# badge.net
KiCad netlist of a schematic drawn in EAGLE
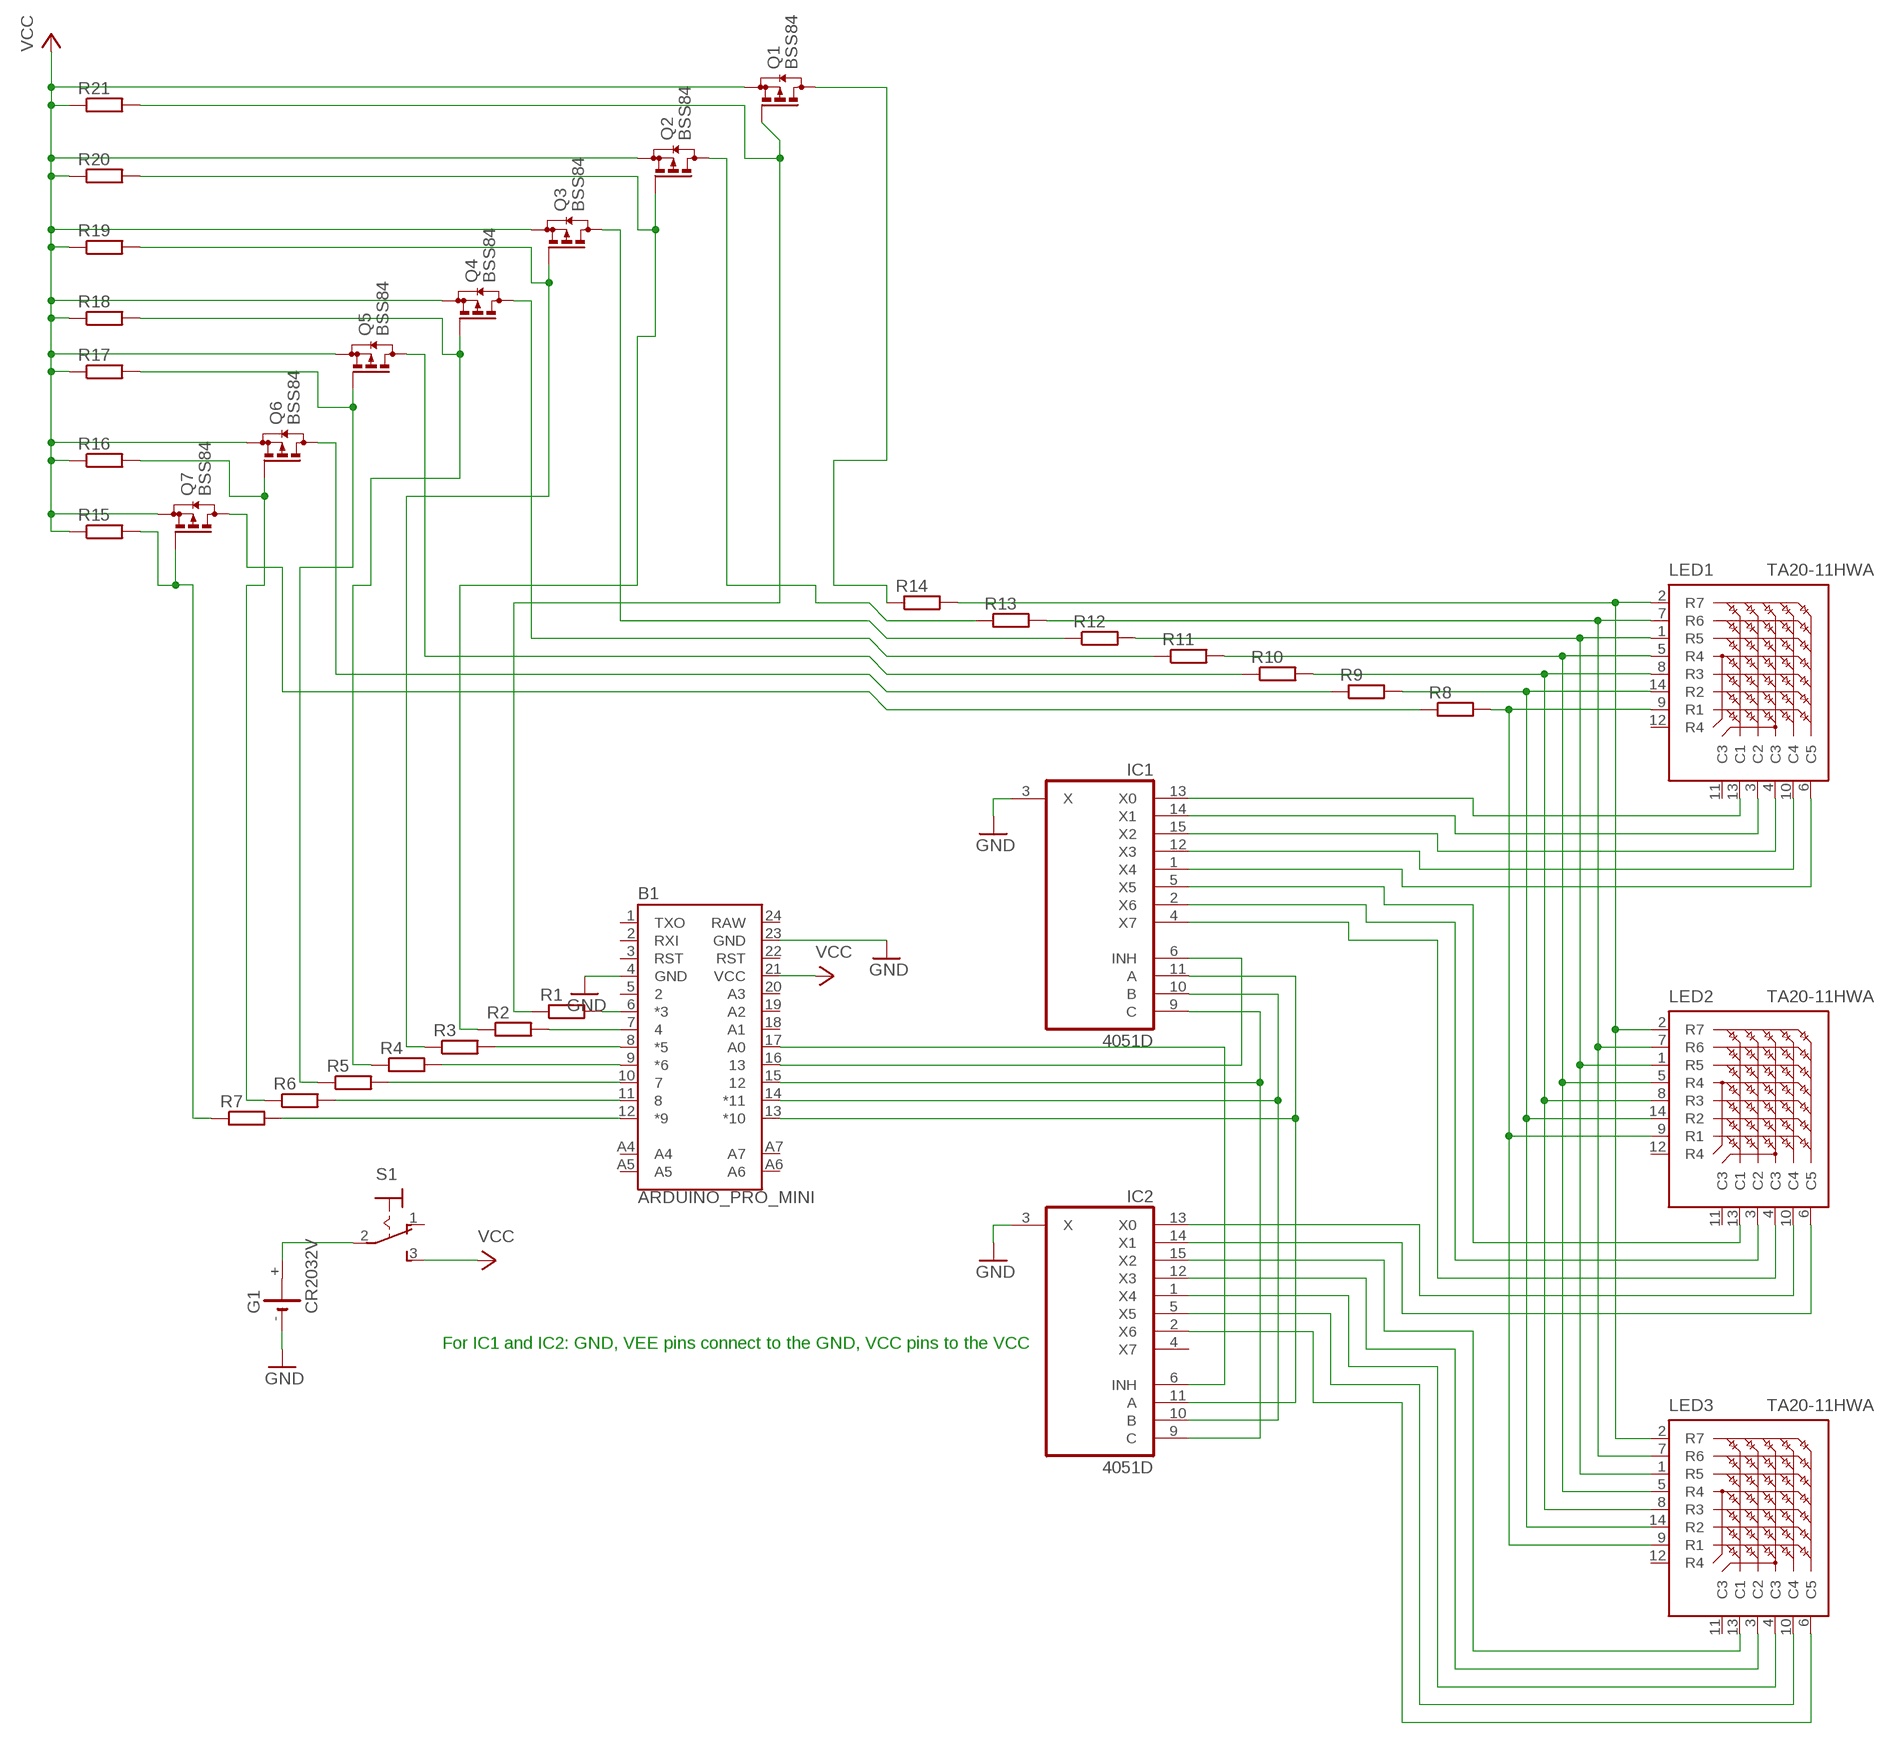
[diagram p0: schematic, sheet 1]

(export (version "E")
  (design (tool "Eeschema 10.0.6"))
  (components
    (comp (ref "B1")
      (value "ARDUINO_PRO_MINI")
      (footprint "eagle-import:ARDUINO_PRO_MINI")
      (libsource (lib "eagle-import") (part "ARDUINO_PRO_MINI"))
    )
    (comp (ref "G1")
      (value "CR2032V")
      (footprint "eagle-import:CR2032V")
      (libsource (lib "eagle-import") (part "CR2032V"))
    )
    (comp (ref "IC1")
      (value "4051D")
      (footprint "eagle-import:SO16")
      (libsource (lib "eagle-import") (part "4051D"))
    )
    (comp (ref "IC2")
      (value "4051D")
      (footprint "eagle-import:SO16")
      (libsource (lib "eagle-import") (part "4051D"))
    )
    (comp (ref "LED1")
      (value "TA20-11HWA")
      (footprint "eagle-import:TA20-11HWA")
      (libsource (lib "eagle-import") (part "TA20-11HWA"))
    )
    (comp (ref "LED2")
      (value "TA20-11HWA")
      (footprint "eagle-import:TA20-11HWA")
      (libsource (lib "eagle-import") (part "TA20-11HWA"))
    )
    (comp (ref "LED3")
      (value "TA20-11HWA")
      (footprint "eagle-import:TA20-11HWA")
      (libsource (lib "eagle-import") (part "TA20-11HWA"))
    )
    (comp (ref "Q1")
      (value "BSS84")
      (footprint "eagle-import:SOT23")
      (libsource (lib "eagle-import") (part "BSS84"))
    )
    (comp (ref "Q2")
      (value "BSS84")
      (footprint "eagle-import:SOT23")
      (libsource (lib "eagle-import") (part "BSS84"))
    )
    (comp (ref "Q3")
      (value "BSS84")
      (footprint "eagle-import:SOT23")
      (libsource (lib "eagle-import") (part "BSS84"))
    )
    (comp (ref "Q4")
      (value "BSS84")
      (footprint "eagle-import:SOT23")
      (libsource (lib "eagle-import") (part "BSS84"))
    )
    (comp (ref "Q5")
      (value "BSS84")
      (footprint "eagle-import:SOT23")
      (libsource (lib "eagle-import") (part "BSS84"))
    )
    (comp (ref "Q6")
      (value "BSS84")
      (footprint "eagle-import:SOT23")
      (libsource (lib "eagle-import") (part "BSS84"))
    )
    (comp (ref "Q7")
      (value "BSS84")
      (footprint "eagle-import:SOT23")
      (libsource (lib "eagle-import") (part "BSS84"))
    )
    (comp (ref "R1")
      (value "R-EU_R0603")
      (footprint "eagle-import:R0603")
      (libsource (lib "eagle-import") (part "R-EU_R0603"))
    )
    (comp (ref "R2")
      (value "R-EU_R0603")
      (footprint "eagle-import:R0603")
      (libsource (lib "eagle-import") (part "R-EU_R0603"))
    )
    (comp (ref "R3")
      (value "R-EU_R0603")
      (footprint "eagle-import:R0603")
      (libsource (lib "eagle-import") (part "R-EU_R0603"))
    )
    (comp (ref "R4")
      (value "R-EU_R0603")
      (footprint "eagle-import:R0603")
      (libsource (lib "eagle-import") (part "R-EU_R0603"))
    )
    (comp (ref "R5")
      (value "R-EU_R0603")
      (footprint "eagle-import:R0603")
      (libsource (lib "eagle-import") (part "R-EU_R0603"))
    )
    (comp (ref "R6")
      (value "R-EU_R0603")
      (footprint "eagle-import:R0603")
      (libsource (lib "eagle-import") (part "R-EU_R0603"))
    )
    (comp (ref "R7")
      (value "R-EU_R0603")
      (footprint "eagle-import:R0603")
      (libsource (lib "eagle-import") (part "R-EU_R0603"))
    )
    (comp (ref "R8")
      (value "R-EU_R0805")
      (footprint "eagle-import:R0805")
      (libsource (lib "eagle-import") (part "resistor_348_R-EU_R0805"))
    )
    (comp (ref "R9")
      (value "R-EU_R0805")
      (footprint "eagle-import:R0805")
      (libsource (lib "eagle-import") (part "resistor_348_R-EU_R0805"))
    )
    (comp (ref "R10")
      (value "R-EU_R0805")
      (footprint "eagle-import:R0805")
      (libsource (lib "eagle-import") (part "resistor_348_R-EU_R0805"))
    )
    (comp (ref "R11")
      (value "R-EU_R0805")
      (footprint "eagle-import:R0805")
      (libsource (lib "eagle-import") (part "resistor_348_R-EU_R0805"))
    )
    (comp (ref "R12")
      (value "R-EU_R0805")
      (footprint "eagle-import:R0805")
      (libsource (lib "eagle-import") (part "resistor_348_R-EU_R0805"))
    )
    (comp (ref "R13")
      (value "R-EU_R0805")
      (footprint "eagle-import:R0805")
      (libsource (lib "eagle-import") (part "resistor_348_R-EU_R0805"))
    )
    (comp (ref "R14")
      (value "R-EU_R0805")
      (footprint "eagle-import:R0805")
      (libsource (lib "eagle-import") (part "resistor_348_R-EU_R0805"))
    )
    (comp (ref "R15")
      (value "R-EU_R0603")
      (footprint "eagle-import:R0603")
      (libsource (lib "eagle-import") (part "resistor_348_R-EU_R0603"))
    )
    (comp (ref "R16")
      (value "R-EU_R0603")
      (footprint "eagle-import:R0603")
      (libsource (lib "eagle-import") (part "resistor_348_R-EU_R0603"))
    )
    (comp (ref "R17")
      (value "R-EU_R0603")
      (footprint "eagle-import:R0603")
      (libsource (lib "eagle-import") (part "resistor_348_R-EU_R0603"))
    )
    (comp (ref "R18")
      (value "R-EU_R0603")
      (footprint "eagle-import:R0603")
      (libsource (lib "eagle-import") (part "resistor_348_R-EU_R0603"))
    )
    (comp (ref "R19")
      (value "R-EU_R0603")
      (footprint "eagle-import:R0603")
      (libsource (lib "eagle-import") (part "resistor_348_R-EU_R0603"))
    )
    (comp (ref "R20")
      (value "R-EU_R0603")
      (footprint "eagle-import:R0603")
      (libsource (lib "eagle-import") (part "resistor_348_R-EU_R0603"))
    )
    (comp (ref "R21")
      (value "R-EU_R0603")
      (footprint "eagle-import:R0603")
      (libsource (lib "eagle-import") (part "resistor_348_R-EU_R0603"))
    )
    (comp (ref "S1")
      (value "320-916")
      (footprint "eagle-import:320-916")
      (libsource (lib "eagle-import") (part "320-916"))
    )
  )
  (nets
    (net (code "1") (name "/RAW") (class "Default")
      (node (ref "B1") (pin "24") (pinfunction "RAW_24") (pintype "power_in"))
    )
    (net (code "2") (name "GND") (class "Default")
      (node (ref "B1") (pin "23") (pinfunction "GND_23") (pintype "power_in"))
      (node (ref "B1") (pin "4") (pinfunction "GND_4") (pintype "power_in"))
      (node (ref "G1") (pin "-") (pinfunction "-_-") (pintype "passive"))
      (node (ref "IC1") (pin "3") (pinfunction "X_3") (pintype "bidirectional"))
      (node (ref "IC2") (pin "3") (pinfunction "X_3") (pintype "bidirectional"))
    )
    (net (code "3") (name "Net-(B1-*3)") (class "Default")
      (node (ref "B1") (pin "6") (pinfunction "*3_6") (pintype "bidirectional"))
      (node (ref "R1") (pin "2") (pinfunction "2_2") (pintype "passive"))
    )
    (net (code "4") (name "Net-(B1-*5)") (class "Default")
      (node (ref "B1") (pin "8") (pinfunction "*5_8") (pintype "bidirectional"))
      (node (ref "R3") (pin "2") (pinfunction "2_2") (pintype "passive"))
    )
    (net (code "5") (name "Net-(B1-*6)") (class "Default")
      (node (ref "B1") (pin "9") (pinfunction "*6_9") (pintype "bidirectional"))
      (node (ref "R4") (pin "2") (pinfunction "2_2") (pintype "passive"))
    )
    (net (code "6") (name "Net-(B1-*9)") (class "Default")
      (node (ref "B1") (pin "12") (pinfunction "*9_12") (pintype "bidirectional"))
      (node (ref "R7") (pin "2") (pinfunction "2_2") (pintype "passive"))
    )
    (net (code "7") (name "Net-(B1-*10)") (class "Default")
      (node (ref "B1") (pin "13") (pinfunction "*10_13") (pintype "bidirectional"))
      (node (ref "IC1") (pin "11") (pinfunction "A_11") (pintype "input"))
      (node (ref "IC2") (pin "11") (pinfunction "A_11") (pintype "input"))
    )
    (net (code "8") (name "Net-(B1-*11)") (class "Default")
      (node (ref "B1") (pin "14") (pinfunction "*11_14") (pintype "bidirectional"))
      (node (ref "IC1") (pin "10") (pinfunction "B_10") (pintype "input"))
      (node (ref "IC2") (pin "10") (pinfunction "B_10") (pintype "input"))
    )
    (net (code "9") (name "Net-(B1-4)") (class "Default")
      (node (ref "B1") (pin "7") (pinfunction "4_7") (pintype "bidirectional"))
      (node (ref "R2") (pin "2") (pinfunction "2_2") (pintype "passive"))
    )
    (net (code "10") (name "Net-(B1-7)") (class "Default")
      (node (ref "B1") (pin "10") (pinfunction "7_10") (pintype "bidirectional"))
      (node (ref "R5") (pin "2") (pinfunction "2_2") (pintype "passive"))
    )
    (net (code "11") (name "Net-(B1-8)") (class "Default")
      (node (ref "B1") (pin "11") (pinfunction "8_11") (pintype "bidirectional"))
      (node (ref "R6") (pin "2") (pinfunction "2_2") (pintype "passive"))
    )
    (net (code "12") (name "Net-(B1-12)") (class "Default")
      (node (ref "B1") (pin "15") (pinfunction "12_15") (pintype "bidirectional"))
      (node (ref "IC1") (pin "9") (pinfunction "C_9") (pintype "input"))
      (node (ref "IC2") (pin "9") (pinfunction "C_9") (pintype "input"))
    )
    (net (code "13") (name "Net-(B1-13)") (class "Default")
      (node (ref "B1") (pin "16") (pinfunction "13_16") (pintype "bidirectional"))
      (node (ref "IC1") (pin "6") (pinfunction "INH_6") (pintype "input"))
    )
    (net (code "14") (name "Net-(B1-A0)") (class "Default")
      (node (ref "B1") (pin "17") (pinfunction "A0_17") (pintype "bidirectional"))
      (node (ref "IC2") (pin "6") (pinfunction "INH_6") (pintype "input"))
    )
    (net (code "15") (name "Net-(IC1A-X0)") (class "Default")
      (node (ref "IC1") (pin "13") (pinfunction "X0_13") (pintype "bidirectional"))
      (node (ref "LED1") (pin "13") (pinfunction "C1_13") (pintype "passive"))
    )
    (net (code "16") (name "Net-(IC1A-X1)") (class "Default")
      (node (ref "IC1") (pin "14") (pinfunction "X1_14") (pintype "bidirectional"))
      (node (ref "LED1") (pin "3") (pinfunction "C2_3") (pintype "passive"))
    )
    (net (code "17") (name "Net-(IC1A-X2)") (class "Default")
      (node (ref "IC1") (pin "15") (pinfunction "X2_15") (pintype "bidirectional"))
      (node (ref "LED1") (pin "4") (pinfunction "C3_4") (pintype "passive"))
    )
    (net (code "18") (name "Net-(IC1A-X3)") (class "Default")
      (node (ref "IC1") (pin "12") (pinfunction "X3_12") (pintype "bidirectional"))
      (node (ref "LED1") (pin "10") (pinfunction "C4_10") (pintype "passive"))
    )
    (net (code "19") (name "Net-(IC1A-X4)") (class "Default")
      (node (ref "IC1") (pin "1") (pinfunction "X4_1") (pintype "bidirectional"))
      (node (ref "LED1") (pin "6") (pinfunction "C5_6") (pintype "passive"))
    )
    (net (code "20") (name "Net-(IC1A-X5)") (class "Default")
      (node (ref "IC1") (pin "5") (pinfunction "X5_5") (pintype "bidirectional"))
      (node (ref "LED2") (pin "13") (pinfunction "C1_13") (pintype "passive"))
    )
    (net (code "21") (name "Net-(IC1A-X6)") (class "Default")
      (node (ref "IC1") (pin "2") (pinfunction "X6_2") (pintype "bidirectional"))
      (node (ref "LED2") (pin "3") (pinfunction "C2_3") (pintype "passive"))
    )
    (net (code "22") (name "Net-(IC1A-X7)") (class "Default")
      (node (ref "IC1") (pin "4") (pinfunction "X7_4") (pintype "bidirectional"))
      (node (ref "LED2") (pin "4") (pinfunction "C3_4") (pintype "passive"))
    )
    (net (code "23") (name "Net-(IC2A-X0)") (class "Default")
      (node (ref "IC2") (pin "13") (pinfunction "X0_13") (pintype "bidirectional"))
      (node (ref "LED2") (pin "10") (pinfunction "C4_10") (pintype "passive"))
    )
    (net (code "24") (name "Net-(IC2A-X1)") (class "Default")
      (node (ref "IC2") (pin "14") (pinfunction "X1_14") (pintype "bidirectional"))
      (node (ref "LED2") (pin "6") (pinfunction "C5_6") (pintype "passive"))
    )
    (net (code "25") (name "Net-(IC2A-X2)") (class "Default")
      (node (ref "IC2") (pin "15") (pinfunction "X2_15") (pintype "bidirectional"))
      (node (ref "LED3") (pin "13") (pinfunction "C1_13") (pintype "passive"))
    )
    (net (code "26") (name "Net-(IC2A-X3)") (class "Default")
      (node (ref "IC2") (pin "12") (pinfunction "X3_12") (pintype "bidirectional"))
      (node (ref "LED3") (pin "3") (pinfunction "C2_3") (pintype "passive"))
    )
    (net (code "27") (name "Net-(IC2A-X4)") (class "Default")
      (node (ref "IC2") (pin "1") (pinfunction "X4_1") (pintype "bidirectional"))
      (node (ref "LED3") (pin "4") (pinfunction "C3_4") (pintype "passive"))
    )
    (net (code "28") (name "Net-(IC2A-X5)") (class "Default")
      (node (ref "IC2") (pin "5") (pinfunction "X5_5") (pintype "bidirectional"))
      (node (ref "LED3") (pin "10") (pinfunction "C4_10") (pintype "passive"))
    )
    (net (code "29") (name "Net-(IC2A-X6)") (class "Default")
      (node (ref "IC2") (pin "2") (pinfunction "X6_2") (pintype "bidirectional"))
      (node (ref "LED3") (pin "6") (pinfunction "C5_6") (pintype "passive"))
    )
    (net (code "30") (name "Net-(LED1-R1)") (class "Default")
      (node (ref "LED1") (pin "9") (pinfunction "R1_9") (pintype "passive"))
      (node (ref "LED2") (pin "9") (pinfunction "R1_9") (pintype "passive"))
      (node (ref "LED3") (pin "9") (pinfunction "R1_9") (pintype "passive"))
      (node (ref "R8") (pin "2") (pinfunction "2_2") (pintype "passive"))
    )
    (net (code "31") (name "Net-(LED1-R2)") (class "Default")
      (node (ref "LED1") (pin "14") (pinfunction "R2_14") (pintype "passive"))
      (node (ref "LED2") (pin "14") (pinfunction "R2_14") (pintype "passive"))
      (node (ref "LED3") (pin "14") (pinfunction "R2_14") (pintype "passive"))
      (node (ref "R9") (pin "2") (pinfunction "2_2") (pintype "passive"))
    )
    (net (code "32") (name "Net-(LED1-R3)") (class "Default")
      (node (ref "LED1") (pin "8") (pinfunction "R3_8") (pintype "passive"))
      (node (ref "LED2") (pin "8") (pinfunction "R3_8") (pintype "passive"))
      (node (ref "LED3") (pin "8") (pinfunction "R3_8") (pintype "passive"))
      (node (ref "R10") (pin "2") (pinfunction "2_2") (pintype "passive"))
    )
    (net (code "33") (name "Net-(LED1-R4-Pad5)") (class "Default")
      (node (ref "LED1") (pin "5") (pinfunction "R4_5") (pintype "passive"))
      (node (ref "LED2") (pin "5") (pinfunction "R4_5") (pintype "passive"))
      (node (ref "LED3") (pin "5") (pinfunction "R4_5") (pintype "passive"))
      (node (ref "R11") (pin "2") (pinfunction "2_2") (pintype "passive"))
    )
    (net (code "34") (name "Net-(LED1-R5)") (class "Default")
      (node (ref "LED1") (pin "1") (pinfunction "R5_1") (pintype "passive"))
      (node (ref "LED2") (pin "1") (pinfunction "R5_1") (pintype "passive"))
      (node (ref "LED3") (pin "1") (pinfunction "R5_1") (pintype "passive"))
      (node (ref "R12") (pin "2") (pinfunction "2_2") (pintype "passive"))
    )
    (net (code "35") (name "Net-(LED1-R6)") (class "Default")
      (node (ref "LED1") (pin "7") (pinfunction "R6_7") (pintype "passive"))
      (node (ref "LED2") (pin "7") (pinfunction "R6_7") (pintype "passive"))
      (node (ref "LED3") (pin "7") (pinfunction "R6_7") (pintype "passive"))
      (node (ref "R13") (pin "2") (pinfunction "2_2") (pintype "passive"))
    )
    (net (code "36") (name "Net-(LED1-R7)") (class "Default")
      (node (ref "LED1") (pin "2") (pinfunction "R7_2") (pintype "passive"))
      (node (ref "LED2") (pin "2") (pinfunction "R7_2") (pintype "passive"))
      (node (ref "LED3") (pin "2") (pinfunction "R7_2") (pintype "passive"))
      (node (ref "R14") (pin "2") (pinfunction "2_2") (pintype "passive"))
    )
    (net (code "37") (name "Net-(Q1-D)") (class "Default")
      (node (ref "Q1") (pin "3") (pinfunction "D_3") (pintype "passive"))
      (node (ref "R14") (pin "1") (pinfunction "1_1") (pintype "passive"))
    )
    (net (code "38") (name "Net-(Q1-G)") (class "Default")
      (node (ref "Q1") (pin "1") (pinfunction "G_1") (pintype "passive"))
      (node (ref "R1") (pin "1") (pinfunction "1_1") (pintype "passive"))
      (node (ref "R21") (pin "2") (pinfunction "2_2") (pintype "passive"))
    )
    (net (code "39") (name "Net-(Q2-D)") (class "Default")
      (node (ref "Q2") (pin "3") (pinfunction "D_3") (pintype "passive"))
      (node (ref "R13") (pin "1") (pinfunction "1_1") (pintype "passive"))
    )
    (net (code "40") (name "Net-(Q2-G)") (class "Default")
      (node (ref "Q2") (pin "1") (pinfunction "G_1") (pintype "passive"))
      (node (ref "R2") (pin "1") (pinfunction "1_1") (pintype "passive"))
      (node (ref "R20") (pin "2") (pinfunction "2_2") (pintype "passive"))
    )
    (net (code "41") (name "Net-(Q3-D)") (class "Default")
      (node (ref "Q3") (pin "3") (pinfunction "D_3") (pintype "passive"))
      (node (ref "R12") (pin "1") (pinfunction "1_1") (pintype "passive"))
    )
    (net (code "42") (name "Net-(Q3-G)") (class "Default")
      (node (ref "Q3") (pin "1") (pinfunction "G_1") (pintype "passive"))
      (node (ref "R19") (pin "2") (pinfunction "2_2") (pintype "passive"))
      (node (ref "R3") (pin "1") (pinfunction "1_1") (pintype "passive"))
    )
    (net (code "43") (name "Net-(Q4-D)") (class "Default")
      (node (ref "Q4") (pin "3") (pinfunction "D_3") (pintype "passive"))
      (node (ref "R11") (pin "1") (pinfunction "1_1") (pintype "passive"))
    )
    (net (code "44") (name "Net-(Q4-G)") (class "Default")
      (node (ref "Q4") (pin "1") (pinfunction "G_1") (pintype "passive"))
      (node (ref "R18") (pin "2") (pinfunction "2_2") (pintype "passive"))
      (node (ref "R4") (pin "1") (pinfunction "1_1") (pintype "passive"))
    )
    (net (code "45") (name "Net-(Q5-D)") (class "Default")
      (node (ref "Q5") (pin "3") (pinfunction "D_3") (pintype "passive"))
      (node (ref "R10") (pin "1") (pinfunction "1_1") (pintype "passive"))
    )
    (net (code "46") (name "Net-(Q5-G)") (class "Default")
      (node (ref "Q5") (pin "1") (pinfunction "G_1") (pintype "passive"))
      (node (ref "R17") (pin "2") (pinfunction "2_2") (pintype "passive"))
      (node (ref "R5") (pin "1") (pinfunction "1_1") (pintype "passive"))
    )
    (net (code "47") (name "Net-(Q6-D)") (class "Default")
      (node (ref "Q6") (pin "3") (pinfunction "D_3") (pintype "passive"))
      (node (ref "R9") (pin "1") (pinfunction "1_1") (pintype "passive"))
    )
    (net (code "48") (name "Net-(Q6-G)") (class "Default")
      (node (ref "Q6") (pin "1") (pinfunction "G_1") (pintype "passive"))
      (node (ref "R16") (pin "2") (pinfunction "2_2") (pintype "passive"))
      (node (ref "R6") (pin "1") (pinfunction "1_1") (pintype "passive"))
    )
    (net (code "49") (name "Net-(Q7-D)") (class "Default")
      (node (ref "Q7") (pin "3") (pinfunction "D_3") (pintype "passive"))
      (node (ref "R8") (pin "1") (pinfunction "1_1") (pintype "passive"))
    )
    (net (code "50") (name "Net-(Q7-G)") (class "Default")
      (node (ref "Q7") (pin "1") (pinfunction "G_1") (pintype "passive"))
      (node (ref "R15") (pin "2") (pinfunction "2_2") (pintype "passive"))
      (node (ref "R7") (pin "1") (pinfunction "1_1") (pintype "passive"))
    )
    (net (code "51") (name "Net-(S1-P)") (class "Default")
      (node (ref "G1") (pin "+") (pinfunction "+_+") (pintype "passive"))
      (node (ref "S1") (pin "2") (pinfunction "P_2") (pintype "passive"))
    )
    (net (code "52") (name "VCC") (class "Default")
      (node (ref "B1") (pin "21") (pinfunction "VCC_21") (pintype "power_in"))
      (node (ref "Q1") (pin "2") (pinfunction "S_2") (pintype "passive"))
      (node (ref "Q2") (pin "2") (pinfunction "S_2") (pintype "passive"))
      (node (ref "Q3") (pin "2") (pinfunction "S_2") (pintype "passive"))
      (node (ref "Q4") (pin "2") (pinfunction "S_2") (pintype "passive"))
      (node (ref "Q5") (pin "2") (pinfunction "S_2") (pintype "passive"))
      (node (ref "Q6") (pin "2") (pinfunction "S_2") (pintype "passive"))
      (node (ref "Q7") (pin "2") (pinfunction "S_2") (pintype "passive"))
      (node (ref "R15") (pin "1") (pinfunction "1_1") (pintype "passive"))
      (node (ref "R16") (pin "1") (pinfunction "1_1") (pintype "passive"))
      (node (ref "R17") (pin "1") (pinfunction "1_1") (pintype "passive"))
      (node (ref "R18") (pin "1") (pinfunction "1_1") (pintype "passive"))
      (node (ref "R19") (pin "1") (pinfunction "1_1") (pintype "passive"))
      (node (ref "R20") (pin "1") (pinfunction "1_1") (pintype "passive"))
      (node (ref "R21") (pin "1") (pinfunction "1_1") (pintype "passive"))
      (node (ref "S1") (pin "3") (pinfunction "S_3") (pintype "passive"))
    )
    (net (code "53") (name "unconnected-(B1-2-Pad5)") (class "Default")
      (node (ref "B1") (pin "5") (pinfunction "2_5") (pintype "bidirectional"))
    )
    (net (code "54") (name "unconnected-(B1-A1-Pad18)") (class "Default")
      (node (ref "B1") (pin "18") (pinfunction "A1_18") (pintype "bidirectional"))
    )
    (net (code "55") (name "unconnected-(B1-A2-Pad19)") (class "Default")
      (node (ref "B1") (pin "19") (pinfunction "A2_19") (pintype "bidirectional"))
    )
    (net (code "56") (name "unconnected-(B1-A3-Pad20)") (class "Default")
      (node (ref "B1") (pin "20") (pinfunction "A3_20") (pintype "bidirectional"))
    )
    (net (code "57") (name "unconnected-(B1-PadA4)") (class "Default")
      (node (ref "B1") (pin "A4") (pinfunction "A4_A4") (pintype "bidirectional"))
    )
    (net (code "58") (name "unconnected-(B1-PadA5)") (class "Default")
      (node (ref "B1") (pin "A5") (pinfunction "A5_A5") (pintype "bidirectional"))
    )
    (net (code "59") (name "unconnected-(B1-PadA6)") (class "Default")
      (node (ref "B1") (pin "A6") (pinfunction "A6_A6") (pintype "bidirectional"))
    )
    (net (code "60") (name "unconnected-(B1-PadA7)") (class "Default")
      (node (ref "B1") (pin "A7") (pinfunction "A7_A7") (pintype "bidirectional"))
    )
    (net (code "61") (name "unconnected-(B1-RST-Pad3)") (class "Default")
      (node (ref "B1") (pin "3") (pinfunction "RST_3") (pintype "bidirectional"))
    )
    (net (code "62") (name "unconnected-(B1-RST-Pad22)") (class "Default")
      (node (ref "B1") (pin "22") (pinfunction "RST_22") (pintype "bidirectional"))
    )
    (net (code "63") (name "unconnected-(B1-RXI-Pad2)") (class "Default")
      (node (ref "B1") (pin "2") (pinfunction "RXI_2") (pintype "bidirectional"))
    )
    (net (code "64") (name "unconnected-(B1-TXO-Pad1)") (class "Default")
      (node (ref "B1") (pin "1") (pinfunction "TXO_1") (pintype "bidirectional"))
    )
    (net (code "65") (name "unconnected-(G1-+-Pad+@1)") (class "Default")
      (node (ref "G1") (pin "+@1") (pinfunction "+_+@1") (pintype "passive"))
    )
    (net (code "66") (name "unconnected-(IC2A-X7-Pad4)") (class "Default")
      (node (ref "IC2") (pin "4") (pinfunction "X7_4") (pintype "bidirectional"))
    )
    (net (code "67") (name "unconnected-(LED1-C3-Pad11)") (class "Default")
      (node (ref "LED1") (pin "11") (pinfunction "C3_11") (pintype "passive"))
    )
    (net (code "68") (name "unconnected-(LED1-R4-Pad12)") (class "Default")
      (node (ref "LED1") (pin "12") (pinfunction "R4_12") (pintype "passive"))
    )
    (net (code "69") (name "unconnected-(LED2-C3-Pad11)") (class "Default")
      (node (ref "LED2") (pin "11") (pinfunction "C3_11") (pintype "passive"))
    )
    (net (code "70") (name "unconnected-(LED2-R4-Pad12)") (class "Default")
      (node (ref "LED2") (pin "12") (pinfunction "R4_12") (pintype "passive"))
    )
    (net (code "71") (name "unconnected-(LED3-C3-Pad11)") (class "Default")
      (node (ref "LED3") (pin "11") (pinfunction "C3_11") (pintype "passive"))
    )
    (net (code "72") (name "unconnected-(LED3-R4-Pad12)") (class "Default")
      (node (ref "LED3") (pin "12") (pinfunction "R4_12") (pintype "passive"))
    )
    (net (code "73") (name "unconnected-(S1-O-Pad1)") (class "Default")
      (node (ref "S1") (pin "1") (pinfunction "O_1") (pintype "passive"))
    )
  )
)
